# humidity.net
KiCad netlist of a schematic drawn in EAGLE
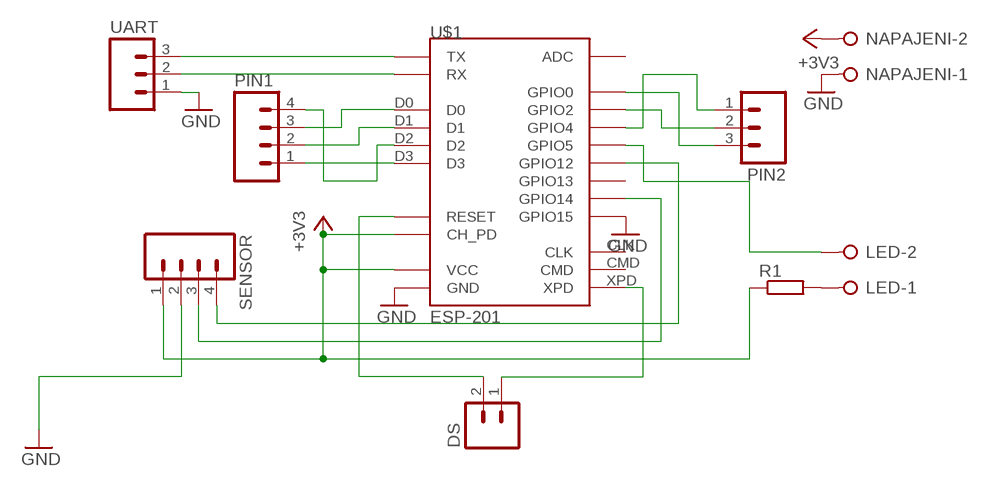
[diagram p0: schematic, sheet 1]

(export (version "E")
  (design (tool "Eeschema 10.0.6"))
  (components
    (comp (ref "DS")
      (value "M02")
      (footprint "eagle-import:02P")
      (libsource (lib "eagle-import") (part "M02"))
    )
    (comp (ref "LED")
      (value "W237-02P")
      (footprint "eagle-import:W237-132")
      (libsource (lib "eagle-import") (part "W237-02P"))
    )
    (comp (ref "NAPAJENI")
      (value "W237-02P")
      (footprint "eagle-import:W237-132")
      (libsource (lib "eagle-import") (part "W237-02P"))
    )
    (comp (ref "PIN1")
      (value "M04")
      (footprint "eagle-import:04P")
      (libsource (lib "eagle-import") (part "M04"))
    )
    (comp (ref "PIN2")
      (value "M03")
      (footprint "eagle-import:03P")
      (libsource (lib "eagle-import") (part "M03"))
    )
    (comp (ref "R1")
      (value "R-EU_0207/7")
      (footprint "eagle-import:0207_7")
      (libsource (lib "eagle-import") (part "R-EU_0207/7"))
    )
    (comp (ref "SENSOR")
      (value "M04")
      (footprint "eagle-import:04P")
      (libsource (lib "eagle-import") (part "M04"))
    )
    (comp (ref "U$1")
      (value "ESP-201")
      (footprint "eagle-import:ESP-201")
      (libsource (lib "eagle-import") (part "ESP-201"))
    )
    (comp (ref "UART")
      (value "M03")
      (footprint "eagle-import:03P")
      (libsource (lib "eagle-import") (part "M03"))
    )
  )
  (nets
    (net (code "1") (name "+3V3") (class "Default")
      (node (ref "NAPAJENI") (pin "2") (pinfunction "KL_2") (pintype "passive"))
      (node (ref "R1") (pin "1") (pinfunction "1_1") (pintype "passive"))
      (node (ref "SENSOR") (pin "1") (pinfunction "1_1") (pintype "passive"))
      (node (ref "U$1") (pin "3V3") (pinfunction "VCC_3V3") (pintype "bidirectional"))
      (node (ref "U$1") (pin "3V3_2") (pinfunction "VCC_3V3_2") (pintype "bidirectional"))
      (node (ref "U$1") (pin "3V3_3") (pinfunction "VCC_3V3_3") (pintype "bidirectional"))
      (node (ref "U$1") (pin "CH_PD") (pinfunction "CH_PD_CH_PD") (pintype "bidirectional"))
    )
    (net (code "2") (name "GND") (class "Default")
      (node (ref "NAPAJENI") (pin "1") (pinfunction "KL_1") (pintype "passive"))
      (node (ref "SENSOR") (pin "2") (pinfunction "2_2") (pintype "passive"))
      (node (ref "U$1") (pin "GND") (pinfunction "GND_GND") (pintype "bidirectional"))
      (node (ref "U$1") (pin "GND_2") (pinfunction "GND_GND_2") (pintype "bidirectional"))
      (node (ref "U$1") (pin "GND_3") (pinfunction "GND_GND_3") (pintype "bidirectional"))
      (node (ref "U$1") (pin "GPIO15") (pinfunction "GPIO15_GPIO15") (pintype "bidirectional"))
      (node (ref "UART") (pin "1") (pinfunction "1_1") (pintype "passive"))
    )
    (net (code "3") (name "Net-(DS-Pad1)") (class "Default")
      (node (ref "DS") (pin "1") (pinfunction "1_1") (pintype "passive"))
      (node (ref "U$1") (pin "XPD") (pinfunction "XPD_XPD") (pintype "bidirectional"))
    )
    (net (code "4") (name "Net-(LEDA-KL)") (class "Default")
      (node (ref "LED") (pin "1") (pinfunction "KL_1") (pintype "passive"))
      (node (ref "R1") (pin "2") (pinfunction "2_2") (pintype "passive"))
    )
    (net (code "5") (name "Net-(LEDB-KL)") (class "Default")
      (node (ref "LED") (pin "2") (pinfunction "KL_2") (pintype "passive"))
      (node (ref "U$1") (pin "GPIO5") (pinfunction "GPIO5_GPIO5") (pintype "bidirectional"))
    )
    (net (code "6") (name "Net-(PIN1-Pad1)") (class "Default")
      (node (ref "PIN1") (pin "1") (pinfunction "1_1") (pintype "passive"))
      (node (ref "U$1") (pin "D3") (pinfunction "D3_D3") (pintype "bidirectional"))
    )
    (net (code "7") (name "Net-(PIN1-Pad2)") (class "Default")
      (node (ref "PIN1") (pin "2") (pinfunction "2_2") (pintype "passive"))
      (node (ref "U$1") (pin "D1") (pinfunction "D1_D1") (pintype "bidirectional"))
    )
    (net (code "8") (name "Net-(PIN1-Pad3)") (class "Default")
      (node (ref "PIN1") (pin "3") (pinfunction "3_3") (pintype "passive"))
      (node (ref "U$1") (pin "D0") (pinfunction "D0_D0") (pintype "bidirectional"))
    )
    (net (code "9") (name "Net-(PIN1-Pad4)") (class "Default")
      (node (ref "PIN1") (pin "4") (pinfunction "4_4") (pintype "passive"))
      (node (ref "U$1") (pin "D2") (pinfunction "D2_D2") (pintype "bidirectional"))
    )
    (net (code "10") (name "Net-(PIN2-Pad1)") (class "Default")
      (node (ref "PIN2") (pin "1") (pinfunction "1_1") (pintype "passive"))
      (node (ref "U$1") (pin "GPIO4") (pinfunction "GPIO4_GPIO4") (pintype "bidirectional"))
    )
    (net (code "11") (name "Net-(PIN2-Pad2)") (class "Default")
      (node (ref "PIN2") (pin "2") (pinfunction "2_2") (pintype "passive"))
      (node (ref "U$1") (pin "GPIO2") (pinfunction "GPIO2_GPIO2") (pintype "bidirectional"))
    )
    (net (code "12") (name "Net-(PIN2-Pad3)") (class "Default")
      (node (ref "PIN2") (pin "3") (pinfunction "3_3") (pintype "passive"))
      (node (ref "U$1") (pin "GPIO0") (pinfunction "GPIO0_GPIO0") (pintype "bidirectional"))
    )
    (net (code "13") (name "Net-(SENSOR-Pad3)") (class "Default")
      (node (ref "SENSOR") (pin "3") (pinfunction "3_3") (pintype "passive"))
      (node (ref "U$1") (pin "GPIO14") (pinfunction "GPIO14_GPIO14") (pintype "bidirectional"))
    )
    (net (code "14") (name "Net-(SENSOR-Pad4)") (class "Default")
      (node (ref "SENSOR") (pin "4") (pinfunction "4_4") (pintype "passive"))
      (node (ref "U$1") (pin "GPIO12") (pinfunction "GPIO12_GPIO12") (pintype "bidirectional"))
    )
    (net (code "15") (name "Net-(U$1-PadRX)") (class "Default")
      (node (ref "U$1") (pin "RX") (pinfunction "RX_RX") (pintype "bidirectional"))
      (node (ref "UART") (pin "2") (pinfunction "2_2") (pintype "passive"))
    )
    (net (code "16") (name "Net-(U$1-PadTX)") (class "Default")
      (node (ref "U$1") (pin "TX") (pinfunction "TX_TX") (pintype "bidirectional"))
      (node (ref "UART") (pin "3") (pinfunction "3_3") (pintype "passive"))
    )
    (net (code "17") (name "Net-(U$1-RESET)") (class "Default")
      (node (ref "DS") (pin "2") (pinfunction "2_2") (pintype "passive"))
      (node (ref "U$1") (pin "RST") (pinfunction "RESET_RST") (pintype "bidirectional"))
    )
    (net (code "18") (name "unconnected-(U$1-PadADC)") (class "Default")
      (node (ref "U$1") (pin "ADC") (pinfunction "ADC_ADC") (pintype "bidirectional"))
    )
    (net (code "19") (name "unconnected-(U$1-PadCLK)") (class "Default")
      (node (ref "U$1") (pin "CLK") (pinfunction "CLK_CLK") (pintype "bidirectional"))
    )
    (net (code "20") (name "unconnected-(U$1-PadCMD)") (class "Default")
      (node (ref "U$1") (pin "CMD") (pinfunction "CMD_CMD") (pintype "bidirectional"))
    )
    (net (code "21") (name "unconnected-(U$1-PadGPIO13)") (class "Default")
      (node (ref "U$1") (pin "GPIO13") (pinfunction "GPIO13_GPIO13") (pintype "bidirectional"))
    )
  )
)
